# MCU.net
KiCad netlist of a schematic drawn in Altium Designer
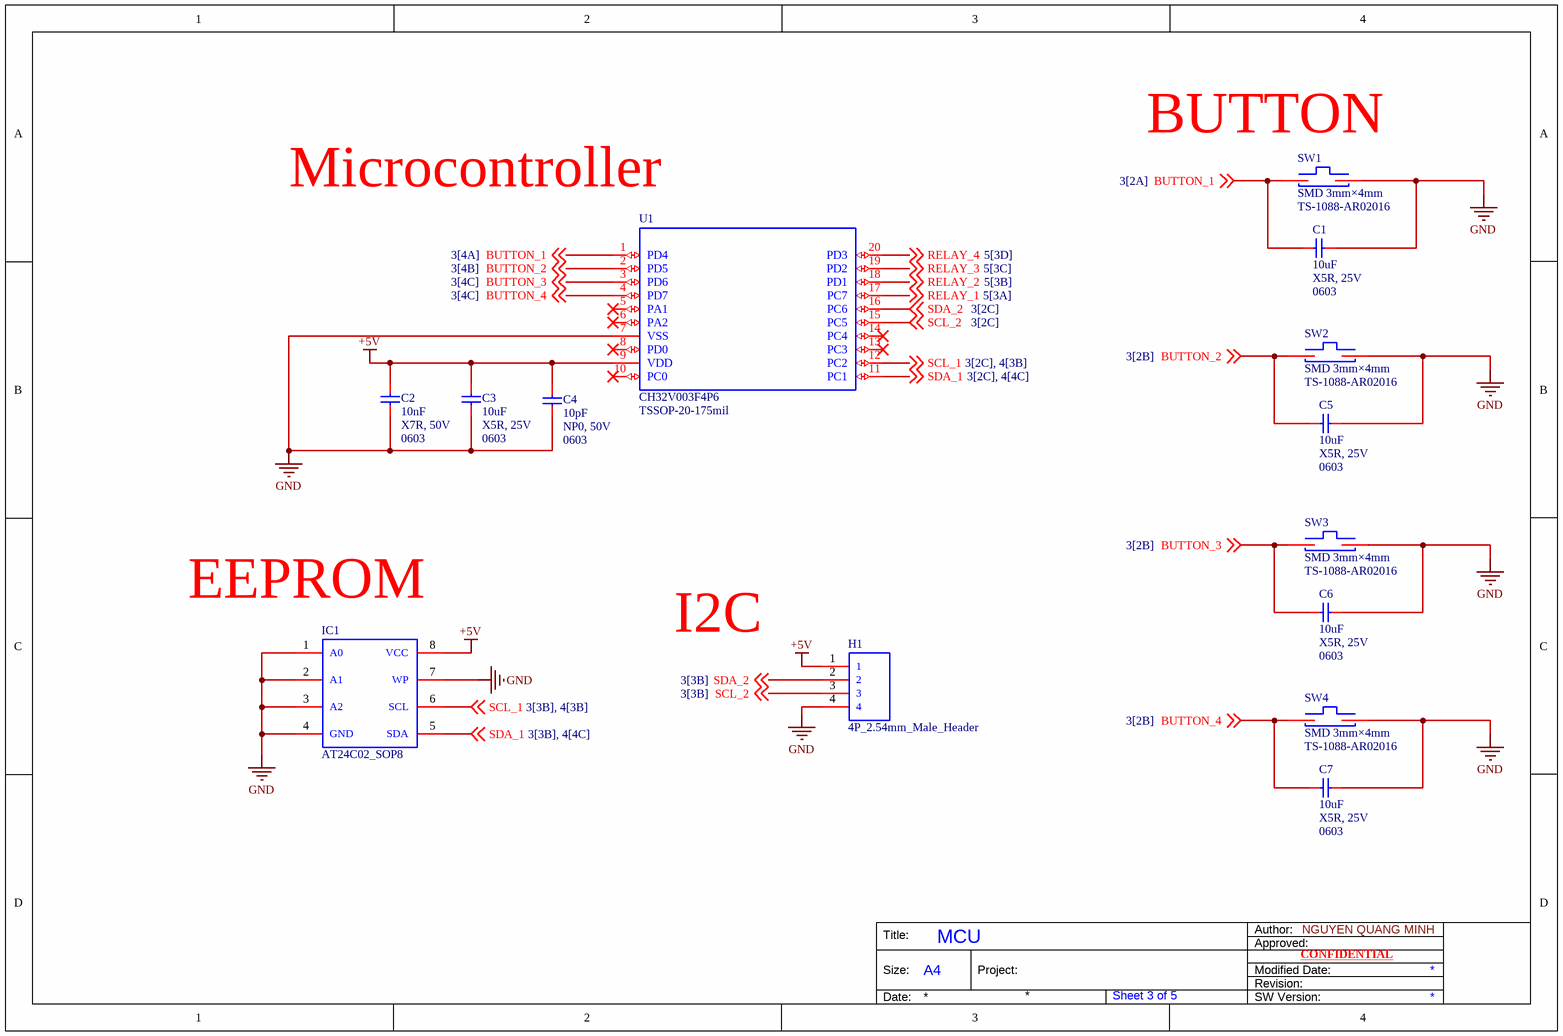
[diagram p0: MCU.SchDoc]

(export (version "E")
  (design (tool "Eeschema 10.0.6"))
  (components
    (comp (ref "C1")
      (value "10uF")
      (footprint "C0603")
      (description "25V 10uF X5R ±20% 0603 Multilayer Ceramic Capacitors MLCC - SMD/SMT ROHS")
      (fields
        (field (name "MANUFACTURER") "YAGEO")
        (field (name "MFR. PART") "CC0603MRX5R8BB106")
        (field (name "TEMPERATURE COEFFICIENT") "X5R, 25V")
        (field (name "PACKAGE") "0603")
      )
      (libsource (lib "Capacitor") (part "C0603_MLCC_10uF_X5R_25V"))
    )
    (comp (ref "C2")
      (value "10nF")
      (footprint "C0603")
      (description "50V 10nF X7R ±10% 0603 Multilayer Ceramic Capacitors MLCC - SMD/SMT ROHS")
      (fields
        (field (name "MANUFACTURER") "YAGEO")
        (field (name "MFR. PART") "CC0603KRX7R9BB103")
        (field (name "TEMPERATURE COEFFICIENT") "X7R, 50V")
        (field (name "PACKAGE") "0603")
      )
      (libsource (lib "Capacitor") (part "C0603_MLCC_10nF_X7R_50V"))
    )
    (comp (ref "C3")
      (value "10uF")
      (footprint "C0603")
      (description "25V 10uF X5R ±20% 0603 Multilayer Ceramic Capacitors MLCC - SMD/SMT ROHS")
      (fields
        (field (name "MANUFACTURER") "YAGEO")
        (field (name "MFR. PART") "CC0603MRX5R8BB106")
        (field (name "TEMPERATURE COEFFICIENT") "X5R, 25V")
        (field (name "PACKAGE") "0603")
      )
      (libsource (lib "Capacitor") (part "C0603_MLCC_10uF_X5R_25V"))
    )
    (comp (ref "C4")
      (value "10pF")
      (footprint "C0603")
      (description "50V 10pF NP0 ±5% 0603 Multilayer Ceramic Capacitors MLCC - SMD/SMT ROHS")
      (fields
        (field (name "MANUFACTURER") "YAGEO")
        (field (name "MFR. PART") "CC0603JRNPO9BN100")
        (field (name "TEMPERATURE COEFFICIENT") "NP0, 50V")
        (field (name "PACKAGE") "0603")
      )
      (libsource (lib "Capacitor") (part "C0603_MLCC_10pF_NP0_50V"))
    )
    (comp (ref "C5")
      (value "10uF")
      (footprint "C0603")
      (description "25V 10uF X5R ±20% 0603 Multilayer Ceramic Capacitors MLCC - SMD/SMT ROHS")
      (fields
        (field (name "MANUFACTURER") "YAGEO")
        (field (name "MFR. PART") "CC0603MRX5R8BB106")
        (field (name "TEMPERATURE COEFFICIENT") "X5R, 25V")
        (field (name "PACKAGE") "0603")
      )
      (libsource (lib "Capacitor") (part "C0603_MLCC_10uF_X5R_25V"))
    )
    (comp (ref "C6")
      (value "10uF")
      (footprint "C0603")
      (description "25V 10uF X5R ±20% 0603 Multilayer Ceramic Capacitors MLCC - SMD/SMT ROHS")
      (fields
        (field (name "MANUFACTURER") "YAGEO")
        (field (name "MFR. PART") "CC0603MRX5R8BB106")
        (field (name "TEMPERATURE COEFFICIENT") "X5R, 25V")
        (field (name "PACKAGE") "0603")
      )
      (libsource (lib "Capacitor") (part "C0603_MLCC_10uF_X5R_25V"))
    )
    (comp (ref "C7")
      (value "10uF")
      (footprint "C0603")
      (description "25V 10uF X5R ±20% 0603 Multilayer Ceramic Capacitors MLCC - SMD/SMT ROHS")
      (fields
        (field (name "MANUFACTURER") "YAGEO")
        (field (name "MFR. PART") "CC0603MRX5R8BB106")
        (field (name "TEMPERATURE COEFFICIENT") "X5R, 25V")
        (field (name "PACKAGE") "0603")
      )
      (libsource (lib "Capacitor") (part "C0603_MLCC_10uF_X5R_25V"))
    )
    (comp (ref "H1")
      (value "4P_2.54mm_Male_Header")
      (footprint "4P, 2,54mm, MALE HEADER")
      (fields
        (field (name "MANUFACTURER") "XFCN")
        (field (name "MFR. PART") "PZ254V-11-04P")
        (field (name "LCSC PART") "C2691448")
      )
      (libsource (lib "HEADER") (part "4P_2.54mm_Male_Header"))
    )
    (comp (ref "IC1")
      (value "AT24C02_SOP8")
      (footprint "SOP-8")
      (description "2Kbit 1.8V~5.5V 1MHz I2C SOP-8 Memory (ICs) ROHS")
      (fields (field (name "MANUFACTURER") "IDCHIP") (field (name "MFR. PART") "AT24C02"))
      (libsource (lib "IC") (part "AT24C02_SOP8"))
    )
    (comp (ref "SW1")
      (value "SMD 3mm×4mm")
      (footprint "ROUND_BUTTON_SMD 3*4mm")
      (fields
        (field (name "MANUFACTURER") "XUNPU")
        (field (name "LCSC PART") "C720477")
        (field (name "MFR. PART") "TS-1088-AR02016")
      )
      (libsource (lib "BUTTON and SWITCH") (part "SW_BUTTON_SMD_3mm×4mm"))
    )
    (comp (ref "SW2")
      (value "SMD 3mm×4mm")
      (footprint "ROUND_BUTTON_SMD 3*4mm")
      (fields
        (field (name "MANUFACTURER") "XUNPU")
        (field (name "LCSC PART") "C720477")
        (field (name "MFR. PART") "TS-1088-AR02016")
      )
      (libsource (lib "BUTTON and SWITCH") (part "SW_BUTTON_SMD_3mm×4mm"))
    )
    (comp (ref "SW3")
      (value "SMD 3mm×4mm")
      (footprint "ROUND_BUTTON_SMD 3*4mm")
      (fields
        (field (name "MANUFACTURER") "XUNPU")
        (field (name "LCSC PART") "C720477")
        (field (name "MFR. PART") "TS-1088-AR02016")
      )
      (libsource (lib "BUTTON and SWITCH") (part "SW_BUTTON_SMD_3mm×4mm"))
    )
    (comp (ref "SW4")
      (value "SMD 3mm×4mm")
      (footprint "ROUND_BUTTON_SMD 3*4mm")
      (fields
        (field (name "MANUFACTURER") "XUNPU")
        (field (name "LCSC PART") "C720477")
        (field (name "MFR. PART") "TS-1088-AR02016")
      )
      (libsource (lib "BUTTON and SWITCH") (part "SW_BUTTON_SMD_3mm×4mm"))
    )
    (comp (ref "U1")
      (value "CH32V003F4P6")
      (footprint "TSSOP-20")
      (description "TSSOP-20-175mil Microcontrollers (MCU/MPU/SOC) ROHS")
      (fields
        (field (name "MANUFACTURER") "WCH")
        (field (name "LCSC PART") "C5187096")
        (field (name "PACKAGE") "TSSOP-20-175mil")
      )
      (libsource (lib "MCU") (part "CH32V003F4P6_TSSOP-20-175mil"))
    )
  )
  (nets
    (net (code "1") (name "+5V") (class "Default")
      (node (ref "C2") (pin "2") (pinfunction "2_2") (pintype "passive"))
      (node (ref "C3") (pin "2") (pinfunction "2_2") (pintype "passive"))
      (node (ref "C4") (pin "2") (pinfunction "2_2") (pintype "passive"))
      (node (ref "H1") (pin "1") (pinfunction "1_1") (pintype "passive"))
      (node (ref "IC1") (pin "8") (pinfunction "VCC_8") (pintype "passive"))
      (node (ref "U1") (pin "9") (pinfunction "VDD_9") (pintype "power_in"))
    )
    (net (code "2") (name "BUTTON_1") (class "Default")
      (node (ref "C1") (pin "1") (pinfunction "1_1") (pintype "passive"))
      (node (ref "SW1") (pin "1") (pinfunction "1_1") (pintype "passive"))
      (node (ref "U1") (pin "1") (pinfunction "PD4_1") (pintype "bidirectional"))
    )
    (net (code "3") (name "BUTTON_2") (class "Default")
      (node (ref "C5") (pin "1") (pinfunction "1_1") (pintype "passive"))
      (node (ref "SW2") (pin "1") (pinfunction "1_1") (pintype "passive"))
      (node (ref "U1") (pin "2") (pinfunction "PD5_2") (pintype "bidirectional"))
    )
    (net (code "4") (name "BUTTON_3") (class "Default")
      (node (ref "C6") (pin "1") (pinfunction "1_1") (pintype "passive"))
      (node (ref "SW3") (pin "1") (pinfunction "1_1") (pintype "passive"))
      (node (ref "U1") (pin "3") (pinfunction "PD6_3") (pintype "bidirectional"))
    )
    (net (code "5") (name "BUTTON_4") (class "Default")
      (node (ref "C7") (pin "1") (pinfunction "1_1") (pintype "passive"))
      (node (ref "SW4") (pin "1") (pinfunction "1_1") (pintype "passive"))
      (node (ref "U1") (pin "4") (pinfunction "PD7_4") (pintype "bidirectional"))
    )
    (net (code "6") (name "GND") (class "Default")
      (node (ref "C1") (pin "2") (pinfunction "2_2") (pintype "passive"))
      (node (ref "C2") (pin "1") (pinfunction "1_1") (pintype "passive"))
      (node (ref "C3") (pin "1") (pinfunction "1_1") (pintype "passive"))
      (node (ref "C4") (pin "1") (pinfunction "1_1") (pintype "passive"))
      (node (ref "C5") (pin "2") (pinfunction "2_2") (pintype "passive"))
      (node (ref "C6") (pin "2") (pinfunction "2_2") (pintype "passive"))
      (node (ref "C7") (pin "2") (pinfunction "2_2") (pintype "passive"))
      (node (ref "H1") (pin "4") (pinfunction "4_4") (pintype "passive"))
      (node (ref "IC1") (pin "1") (pinfunction "A0_1") (pintype "passive"))
      (node (ref "IC1") (pin "2") (pinfunction "A1_2") (pintype "passive"))
      (node (ref "IC1") (pin "3") (pinfunction "A2_3") (pintype "passive"))
      (node (ref "IC1") (pin "4") (pinfunction "GND_4") (pintype "passive"))
      (node (ref "IC1") (pin "7") (pinfunction "WP_7") (pintype "passive"))
      (node (ref "SW1") (pin "2") (pinfunction "2_2") (pintype "passive"))
      (node (ref "SW2") (pin "2") (pinfunction "2_2") (pintype "passive"))
      (node (ref "SW3") (pin "2") (pinfunction "2_2") (pintype "passive"))
      (node (ref "SW4") (pin "2") (pinfunction "2_2") (pintype "passive"))
      (node (ref "U1") (pin "7") (pinfunction "VSS_7") (pintype "power_in"))
    )
    (net (code "7") (name "RELAY_1") (class "Default")
      (node (ref "U1") (pin "17") (pinfunction "PC7_17") (pintype "bidirectional"))
    )
    (net (code "8") (name "RELAY_2") (class "Default")
      (node (ref "U1") (pin "18") (pinfunction "PD1_18") (pintype "bidirectional"))
    )
    (net (code "9") (name "RELAY_3") (class "Default")
      (node (ref "U1") (pin "19") (pinfunction "PD2_19") (pintype "bidirectional"))
    )
    (net (code "10") (name "RELAY_4") (class "Default")
      (node (ref "U1") (pin "20") (pinfunction "PD3_20") (pintype "bidirectional"))
    )
    (net (code "11") (name "SCL_1") (class "Default")
      (node (ref "IC1") (pin "6") (pinfunction "SCL_6") (pintype "passive"))
      (node (ref "U1") (pin "12") (pinfunction "PC2_12") (pintype "bidirectional"))
    )
    (net (code "12") (name "SCL_2") (class "Default")
      (node (ref "H1") (pin "3") (pinfunction "3_3") (pintype "passive"))
      (node (ref "U1") (pin "15") (pinfunction "PC5_15") (pintype "bidirectional"))
    )
    (net (code "13") (name "SDA_1") (class "Default")
      (node (ref "IC1") (pin "5") (pinfunction "SDA_5") (pintype "passive"))
      (node (ref "U1") (pin "11") (pinfunction "PC1_11") (pintype "bidirectional"))
    )
    (net (code "14") (name "SDA_2") (class "Default")
      (node (ref "H1") (pin "2") (pinfunction "2_2") (pintype "passive"))
      (node (ref "U1") (pin "16") (pinfunction "PC6_16") (pintype "bidirectional"))
    )
    (net (code "15") (name "unconnected-(U1-PA1-Pad5)") (class "Default")
      (node (ref "U1") (pin "5") (pinfunction "PA1_5") (pintype "bidirectional+no_connect"))
    )
    (net (code "16") (name "unconnected-(U1-PA2-Pad6)") (class "Default")
      (node (ref "U1") (pin "6") (pinfunction "PA2_6") (pintype "bidirectional+no_connect"))
    )
    (net (code "17") (name "unconnected-(U1-PC0-Pad10)") (class "Default")
      (node (ref "U1") (pin "10") (pinfunction "PC0_10") (pintype "bidirectional+no_connect"))
    )
    (net (code "18") (name "unconnected-(U1-PC3-Pad13)") (class "Default")
      (node (ref "U1") (pin "13") (pinfunction "PC3_13") (pintype "bidirectional+no_connect"))
    )
    (net (code "19") (name "unconnected-(U1-PC4-Pad14)") (class "Default")
      (node (ref "U1") (pin "14") (pinfunction "PC4_14") (pintype "bidirectional+no_connect"))
    )
    (net (code "20") (name "unconnected-(U1-PD0-Pad8)") (class "Default")
      (node (ref "U1") (pin "8") (pinfunction "PD0_8") (pintype "bidirectional+no_connect"))
    )
  )
)
